# programmer-shield.net
KiCad netlist of a schematic drawn in EAGLE
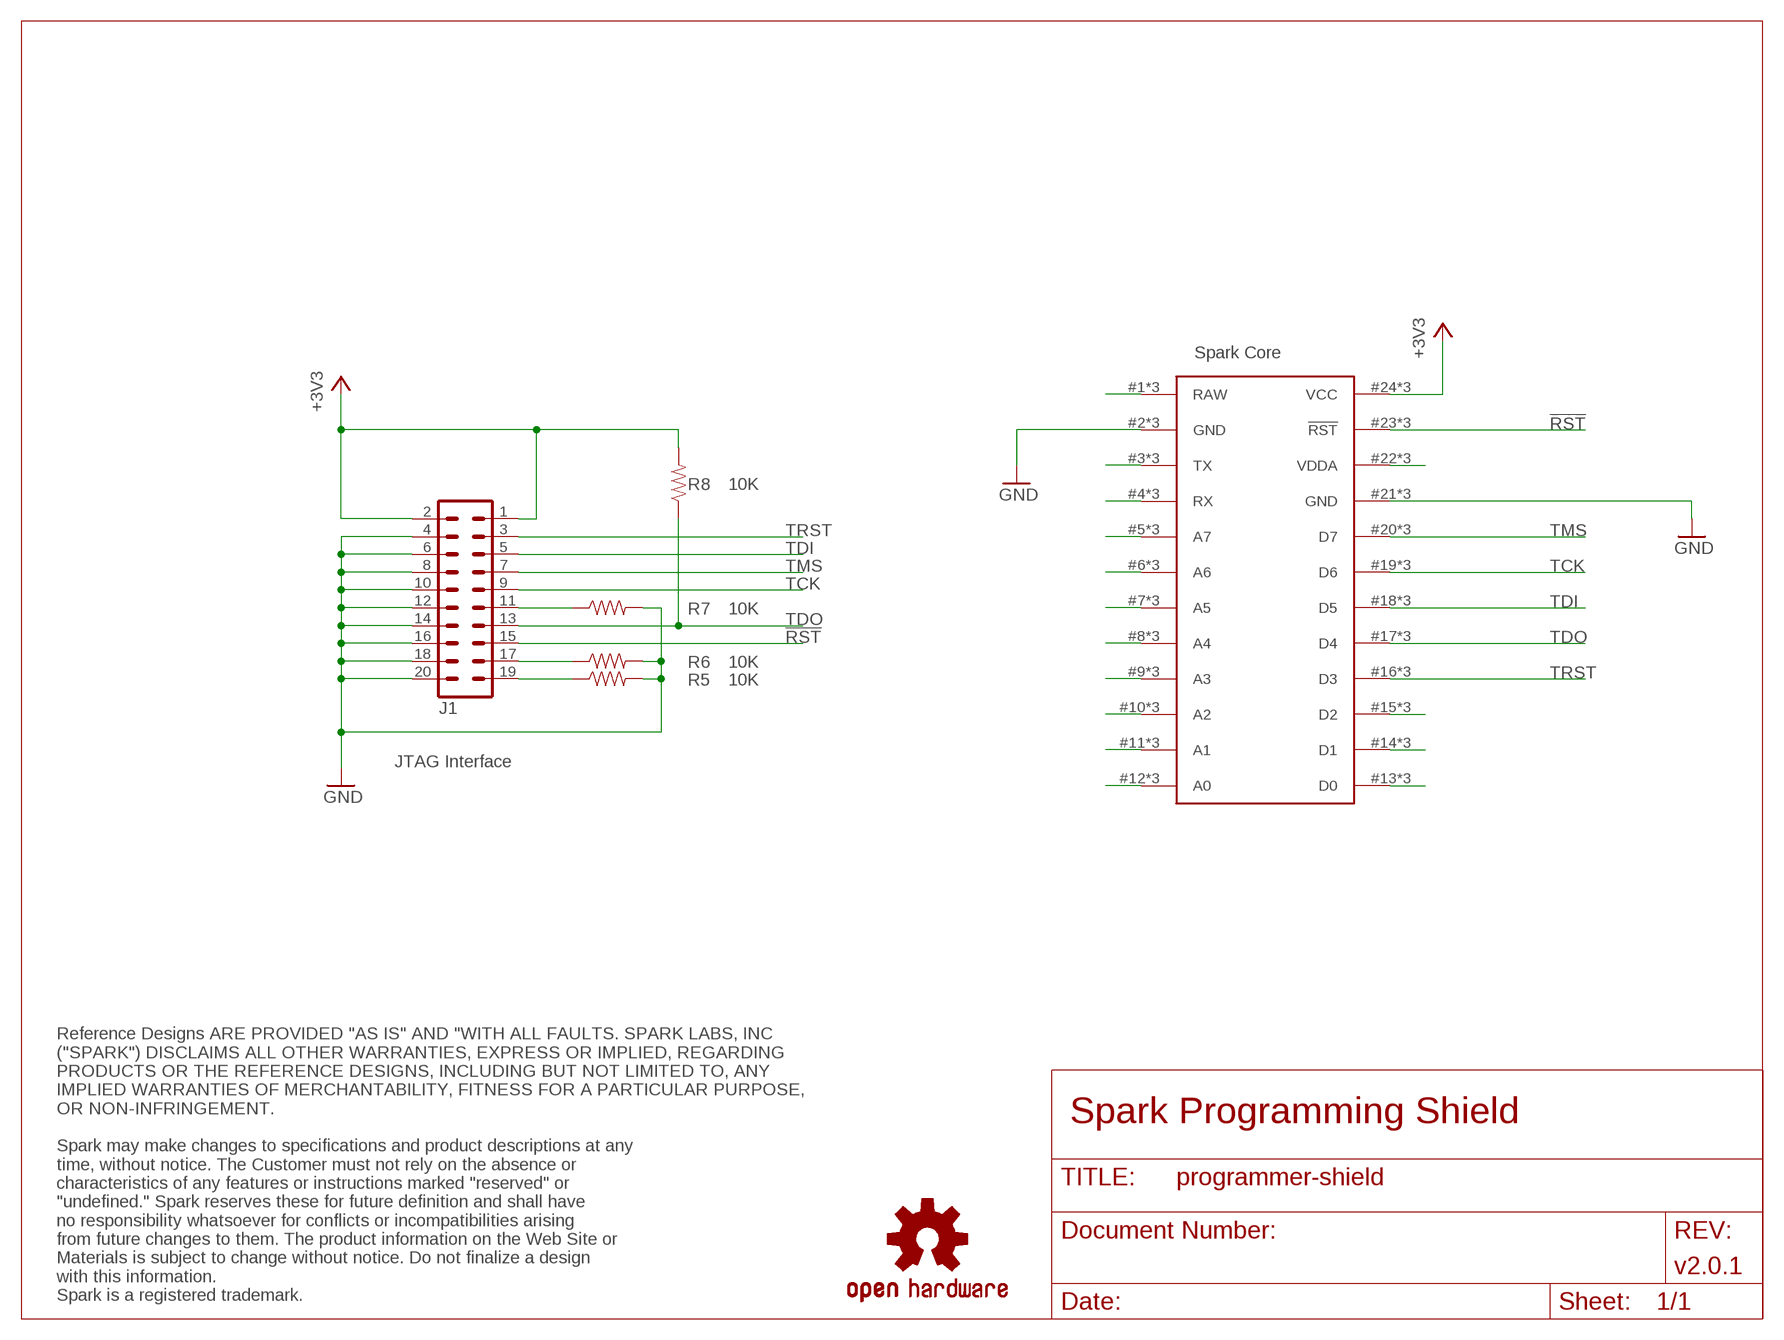
[diagram p0: schematic, sheet 1]

(export (version "E")
  (design (tool "Eeschema 10.0.6"))
  (components
    (comp (ref "J1")
      (value "ML20")
      (footprint "eagle-import:ML20")
      (libsource (lib "eagle-import") (part "ML20"))
    )
    (comp (ref "LOGO1")
      (value "OSHW-LOGOM")
      (footprint "eagle-import:OSHW-LOGO-M")
      (libsource (lib "eagle-import") (part "OSHW-LOGOM"))
    )
    (comp (ref "R5")
      (value "10K")
      (footprint "eagle-import:AXIAL-0.3")
      (libsource (lib "eagle-import") (part "RESISTORAXIAL-0.3"))
    )
    (comp (ref "R6")
      (value "10K")
      (footprint "eagle-import:AXIAL-0.3")
      (libsource (lib "eagle-import") (part "RESISTORAXIAL-0.3"))
    )
    (comp (ref "R7")
      (value "10K")
      (footprint "eagle-import:AXIAL-0.3")
      (libsource (lib "eagle-import") (part "RESISTORAXIAL-0.3"))
    )
    (comp (ref "R8")
      (value "10K")
      (footprint "eagle-import:AXIAL-0.3")
      (libsource (lib "eagle-import") (part "RESISTORAXIAL-0.3"))
    )
    (comp (ref "U$1")
      (value "SPARK_CORE")
      (footprint "eagle-import:SPARK_CORE_STACKABLE")
      (libsource (lib "eagle-import") (part "SPARK_CORE"))
    )
  )
  (nets
    (net (code "1") (name "+3V3") (class "Default")
      (node (ref "J1") (pin "1") (pinfunction "1_1") (pintype "passive"))
      (node (ref "J1") (pin "2") (pinfunction "2_2") (pintype "passive"))
      (node (ref "R8") (pin "P$2") (pinfunction "2_P$2") (pintype "passive"))
      (node (ref "U$1") (pin "#24") (pinfunction "VCC_#24") (pintype "power_in"))
      (node (ref "U$1") (pin "24") (pinfunction "VCC_24") (pintype "power_in"))
      (node (ref "U$1") (pin "@24") (pinfunction "VCC_@24") (pintype "power_in"))
    )
    (net (code "2") (name "/TCK") (class "Default")
      (node (ref "J1") (pin "9") (pinfunction "9_9") (pintype "passive"))
      (node (ref "U$1") (pin "#19") (pinfunction "D6_#19") (pintype "bidirectional"))
      (node (ref "U$1") (pin "19") (pinfunction "D6_19") (pintype "bidirectional"))
      (node (ref "U$1") (pin "@19") (pinfunction "D6_@19") (pintype "bidirectional"))
    )
    (net (code "3") (name "/TDI") (class "Default")
      (node (ref "J1") (pin "5") (pinfunction "5_5") (pintype "passive"))
      (node (ref "U$1") (pin "#18") (pinfunction "D5_#18") (pintype "bidirectional"))
      (node (ref "U$1") (pin "18") (pinfunction "D5_18") (pintype "bidirectional"))
      (node (ref "U$1") (pin "@18") (pinfunction "D5_@18") (pintype "bidirectional"))
    )
    (net (code "4") (name "/TDO") (class "Default")
      (node (ref "J1") (pin "13") (pinfunction "13_13") (pintype "passive"))
      (node (ref "R8") (pin "P$1") (pinfunction "1_P$1") (pintype "passive"))
      (node (ref "U$1") (pin "#17") (pinfunction "D4_#17") (pintype "bidirectional"))
      (node (ref "U$1") (pin "17") (pinfunction "D4_17") (pintype "bidirectional"))
      (node (ref "U$1") (pin "@17") (pinfunction "D4_@17") (pintype "bidirectional"))
    )
    (net (code "5") (name "/TMS") (class "Default")
      (node (ref "J1") (pin "7") (pinfunction "7_7") (pintype "passive"))
      (node (ref "U$1") (pin "#20") (pinfunction "D7_#20") (pintype "bidirectional"))
      (node (ref "U$1") (pin "20") (pinfunction "D7_20") (pintype "bidirectional"))
      (node (ref "U$1") (pin "@20") (pinfunction "D7_@20") (pintype "bidirectional"))
    )
    (net (code "6") (name "/TRST") (class "Default")
      (node (ref "J1") (pin "3") (pinfunction "3_3") (pintype "passive"))
      (node (ref "U$1") (pin "#16") (pinfunction "D3_#16") (pintype "bidirectional"))
      (node (ref "U$1") (pin "16") (pinfunction "D3_16") (pintype "bidirectional"))
      (node (ref "U$1") (pin "@16") (pinfunction "D3_@16") (pintype "bidirectional"))
    )
    (net (code "7") (name "/~{RST}") (class "Default")
      (node (ref "J1") (pin "15") (pinfunction "15_15") (pintype "passive"))
      (node (ref "U$1") (pin "#23") (pinfunction "~{RST}_#23") (pintype "bidirectional"))
      (node (ref "U$1") (pin "23") (pinfunction "~{RST}_23") (pintype "bidirectional"))
      (node (ref "U$1") (pin "@23") (pinfunction "~{RST}_@23") (pintype "bidirectional"))
    )
    (net (code "8") (name "GND") (class "Default")
      (node (ref "J1") (pin "10") (pinfunction "10_10") (pintype "passive"))
      (node (ref "J1") (pin "12") (pinfunction "12_12") (pintype "passive"))
      (node (ref "J1") (pin "14") (pinfunction "14_14") (pintype "passive"))
      (node (ref "J1") (pin "16") (pinfunction "16_16") (pintype "passive"))
      (node (ref "J1") (pin "18") (pinfunction "18_18") (pintype "passive"))
      (node (ref "J1") (pin "20") (pinfunction "20_20") (pintype "passive"))
      (node (ref "J1") (pin "4") (pinfunction "4_4") (pintype "passive"))
      (node (ref "J1") (pin "6") (pinfunction "6_6") (pintype "passive"))
      (node (ref "J1") (pin "8") (pinfunction "8_8") (pintype "passive"))
      (node (ref "R5") (pin "P$2") (pinfunction "2_P$2") (pintype "passive"))
      (node (ref "R6") (pin "P$2") (pinfunction "2_P$2") (pintype "passive"))
      (node (ref "R7") (pin "P$2") (pinfunction "2_P$2") (pintype "passive"))
      (node (ref "U$1") (pin "#2") (pinfunction "GND_#2") (pintype "power_in"))
      (node (ref "U$1") (pin "#21") (pinfunction "GND_#21") (pintype "power_in"))
      (node (ref "U$1") (pin "2") (pinfunction "GND_2") (pintype "power_in"))
      (node (ref "U$1") (pin "21") (pinfunction "GND_21") (pintype "power_in"))
      (node (ref "U$1") (pin "@2") (pinfunction "GND_@2") (pintype "power_in"))
      (node (ref "U$1") (pin "@21") (pinfunction "GND_@21") (pintype "power_in"))
    )
    (net (code "9") (name "Net-(R5-1)") (class "Default")
      (node (ref "J1") (pin "19") (pinfunction "19_19") (pintype "passive"))
      (node (ref "R5") (pin "P$1") (pinfunction "1_P$1") (pintype "passive"))
    )
    (net (code "10") (name "Net-(R6-1)") (class "Default")
      (node (ref "J1") (pin "17") (pinfunction "17_17") (pintype "passive"))
      (node (ref "R6") (pin "P$1") (pinfunction "1_P$1") (pintype "passive"))
    )
    (net (code "11") (name "Net-(R7-1)") (class "Default")
      (node (ref "J1") (pin "11") (pinfunction "11_11") (pintype "passive"))
      (node (ref "R7") (pin "P$1") (pinfunction "1_P$1") (pintype "passive"))
    )
    (net (code "12") (name "Net-(U$1-A0-Pad#12)") (class "Default")
      (node (ref "U$1") (pin "#12") (pinfunction "A0_#12") (pintype "bidirectional"))
      (node (ref "U$1") (pin "12") (pinfunction "A0_12") (pintype "bidirectional"))
      (node (ref "U$1") (pin "@12") (pinfunction "A0_@12") (pintype "bidirectional"))
    )
    (net (code "13") (name "Net-(U$1-A1-Pad#11)") (class "Default")
      (node (ref "U$1") (pin "#11") (pinfunction "A1_#11") (pintype "bidirectional"))
      (node (ref "U$1") (pin "11") (pinfunction "A1_11") (pintype "bidirectional"))
      (node (ref "U$1") (pin "@11") (pinfunction "A1_@11") (pintype "bidirectional"))
    )
    (net (code "14") (name "Net-(U$1-A2-Pad#10)") (class "Default")
      (node (ref "U$1") (pin "#10") (pinfunction "A2_#10") (pintype "bidirectional"))
      (node (ref "U$1") (pin "10") (pinfunction "A2_10") (pintype "bidirectional"))
      (node (ref "U$1") (pin "@10") (pinfunction "A2_@10") (pintype "bidirectional"))
    )
    (net (code "15") (name "Net-(U$1-A3-Pad#9)") (class "Default")
      (node (ref "U$1") (pin "#9") (pinfunction "A3_#9") (pintype "bidirectional"))
      (node (ref "U$1") (pin "9") (pinfunction "A3_9") (pintype "bidirectional"))
      (node (ref "U$1") (pin "@9") (pinfunction "A3_@9") (pintype "bidirectional"))
    )
    (net (code "16") (name "Net-(U$1-A4-Pad#8)") (class "Default")
      (node (ref "U$1") (pin "#8") (pinfunction "A4_#8") (pintype "bidirectional"))
      (node (ref "U$1") (pin "8") (pinfunction "A4_8") (pintype "bidirectional"))
      (node (ref "U$1") (pin "@8") (pinfunction "A4_@8") (pintype "bidirectional"))
    )
    (net (code "17") (name "Net-(U$1-A5-Pad#7)") (class "Default")
      (node (ref "U$1") (pin "#7") (pinfunction "A5_#7") (pintype "bidirectional"))
      (node (ref "U$1") (pin "7") (pinfunction "A5_7") (pintype "bidirectional"))
      (node (ref "U$1") (pin "@7") (pinfunction "A5_@7") (pintype "bidirectional"))
    )
    (net (code "18") (name "Net-(U$1-A6-Pad#6)") (class "Default")
      (node (ref "U$1") (pin "#6") (pinfunction "A6_#6") (pintype "bidirectional"))
      (node (ref "U$1") (pin "6") (pinfunction "A6_6") (pintype "bidirectional"))
      (node (ref "U$1") (pin "@6") (pinfunction "A6_@6") (pintype "bidirectional"))
    )
    (net (code "19") (name "Net-(U$1-A7-Pad#5)") (class "Default")
      (node (ref "U$1") (pin "#5") (pinfunction "A7_#5") (pintype "bidirectional"))
      (node (ref "U$1") (pin "5") (pinfunction "A7_5") (pintype "bidirectional"))
      (node (ref "U$1") (pin "@5") (pinfunction "A7_@5") (pintype "bidirectional"))
    )
    (net (code "20") (name "Net-(U$1-D0-Pad#13)") (class "Default")
      (node (ref "U$1") (pin "#13") (pinfunction "D0_#13") (pintype "bidirectional"))
      (node (ref "U$1") (pin "13") (pinfunction "D0_13") (pintype "bidirectional"))
      (node (ref "U$1") (pin "@13") (pinfunction "D0_@13") (pintype "bidirectional"))
    )
    (net (code "21") (name "Net-(U$1-D1-Pad#14)") (class "Default")
      (node (ref "U$1") (pin "#14") (pinfunction "D1_#14") (pintype "bidirectional"))
      (node (ref "U$1") (pin "14") (pinfunction "D1_14") (pintype "bidirectional"))
      (node (ref "U$1") (pin "@14") (pinfunction "D1_@14") (pintype "bidirectional"))
    )
    (net (code "22") (name "Net-(U$1-D2-Pad#15)") (class "Default")
      (node (ref "U$1") (pin "#15") (pinfunction "D2_#15") (pintype "bidirectional"))
      (node (ref "U$1") (pin "15") (pinfunction "D2_15") (pintype "bidirectional"))
      (node (ref "U$1") (pin "@15") (pinfunction "D2_@15") (pintype "bidirectional"))
    )
    (net (code "23") (name "Net-(U$1-RAW-Pad#1)") (class "Default")
      (node (ref "U$1") (pin "#1") (pinfunction "RAW_#1") (pintype "power_in"))
      (node (ref "U$1") (pin "1") (pinfunction "RAW_1") (pintype "power_in"))
      (node (ref "U$1") (pin "@1") (pinfunction "RAW_@1") (pintype "power_in"))
    )
    (net (code "24") (name "Net-(U$1-RX-Pad#4)") (class "Default")
      (node (ref "U$1") (pin "#4") (pinfunction "RX_#4") (pintype "bidirectional"))
      (node (ref "U$1") (pin "4") (pinfunction "RX_4") (pintype "bidirectional"))
      (node (ref "U$1") (pin "@4") (pinfunction "RX_@4") (pintype "bidirectional"))
    )
    (net (code "25") (name "Net-(U$1-TX-Pad#3)") (class "Default")
      (node (ref "U$1") (pin "#3") (pinfunction "TX_#3") (pintype "bidirectional"))
      (node (ref "U$1") (pin "3") (pinfunction "TX_3") (pintype "bidirectional"))
      (node (ref "U$1") (pin "@3") (pinfunction "TX_@3") (pintype "bidirectional"))
    )
    (net (code "26") (name "Net-(U$1-VDDA-Pad#22)") (class "Default")
      (node (ref "U$1") (pin "#22") (pinfunction "VDDA_#22") (pintype "power_in"))
      (node (ref "U$1") (pin "22") (pinfunction "VDDA_22") (pintype "power_in"))
      (node (ref "U$1") (pin "@22") (pinfunction "VDDA_@22") (pintype "power_in"))
    )
  )
)
